# SCH_Project-SappY_2026-01-23.net
KiCad netlist of a schematic drawn in EasyEDA
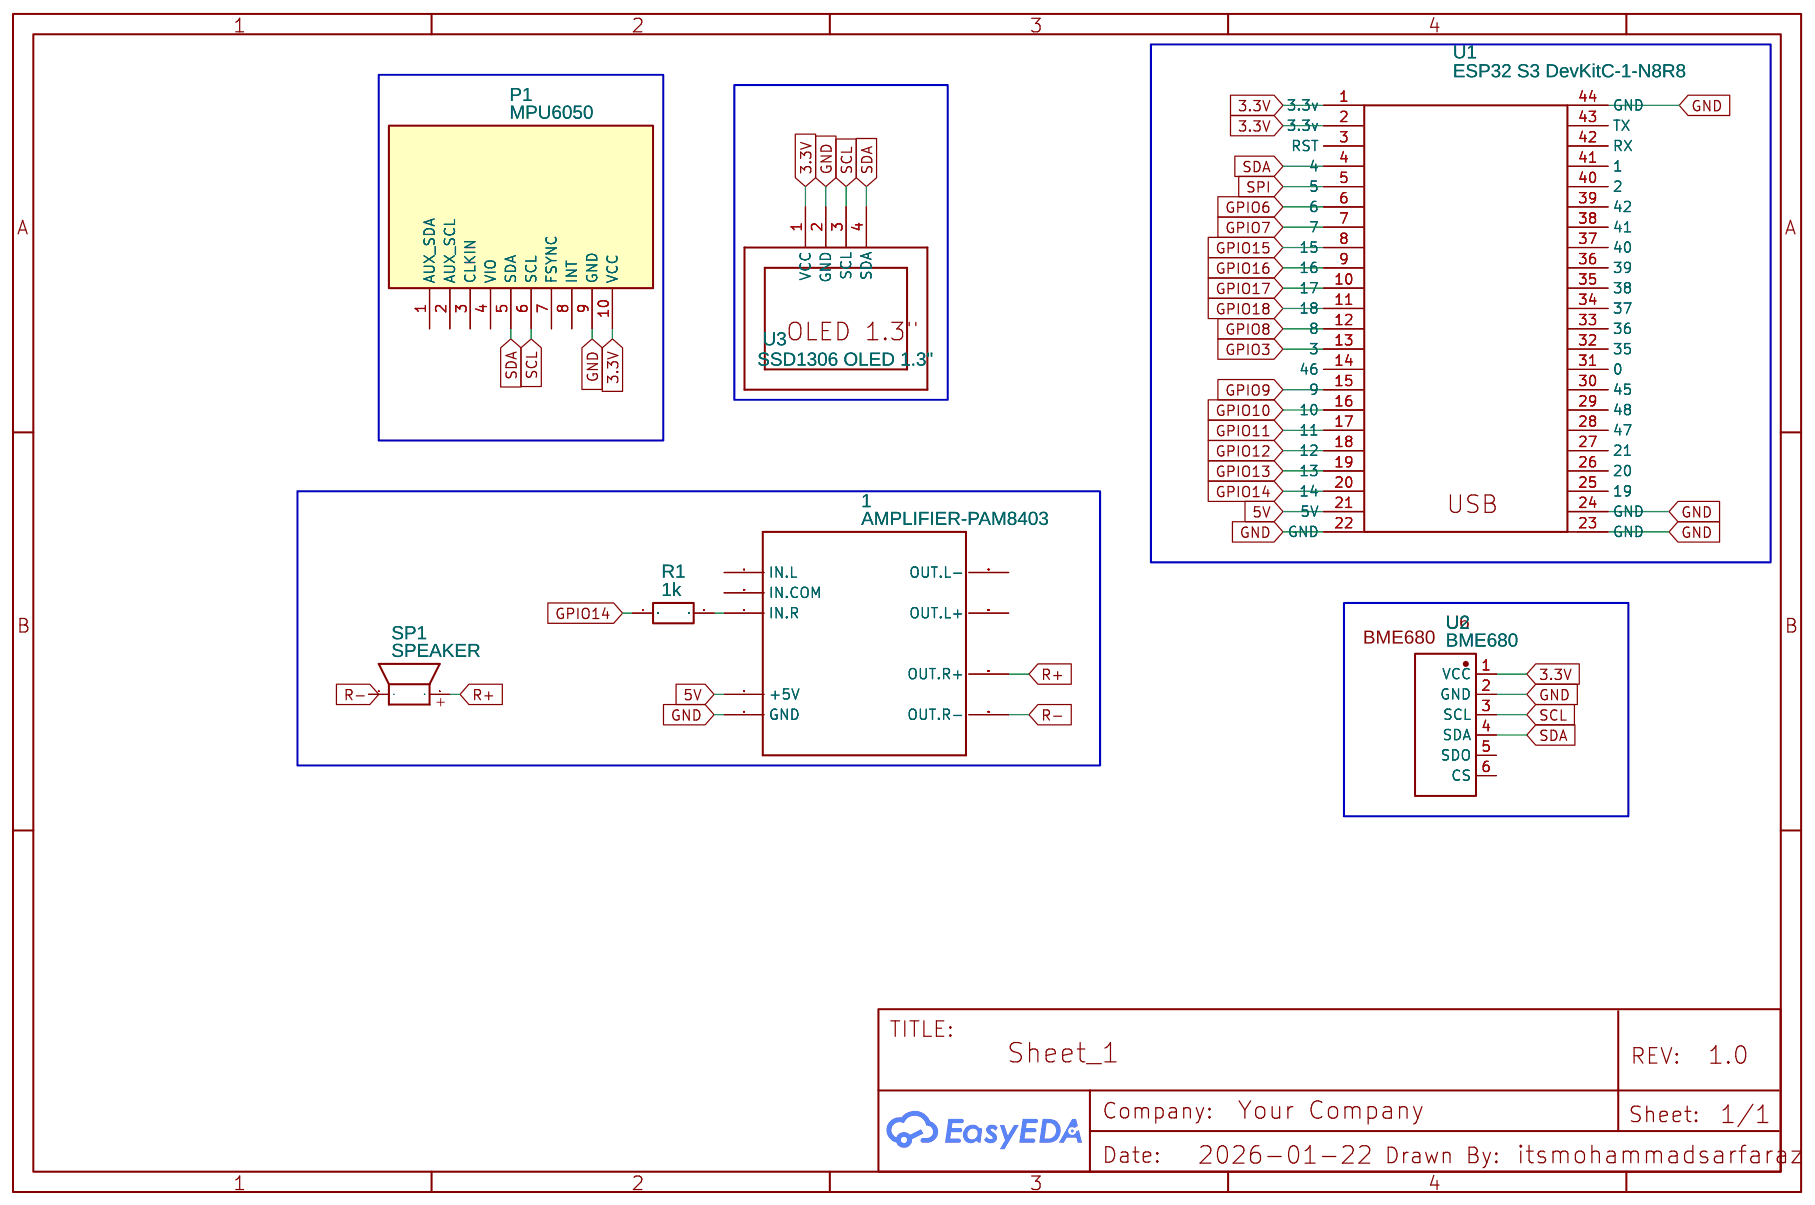
[diagram p0: schematic sheet]

(export (version "E")
  (design (tool "Eeschema 10.0.6"))
  (components
    (comp (ref "1") (value "AMPLIFIER-PAM8403") (libsource (lib "") (part "AMPLIFIER-PAM8403")))
    (comp (ref "P1") (value "MPU6050") (libsource (lib "") (part "MPU6050")))
    (comp (ref "R1") (value "1k") (libsource (lib "") (part "R_0603_EU")))
    (comp (ref "SP1") (value "SPEAKER") (libsource (lib "") (part "SPEAKER")))
    (comp (ref "U1") (value "ESP32 S3 DevKitC-1-N8R8") (libsource (lib "") (part "ESP32 S3 DevKitC-1-N8R8")))
    (comp (ref "U2") (value "BME680") (libsource (lib "") (part "BME680")))
    (comp (ref "U3") (value "SSD1306 OLED 1.3\"") (libsource (lib "") (part "SSD1306 OLED 1.3{dblquote}")))
  )
  (nets
    (net (code "1") (name "3.3V") (class "Default")
      (node (ref "P1") (pin "10") (pinfunction "VCC_10") (pintype "unspecified"))
      (node (ref "U1") (pin "1") (pinfunction "3.3v_1") (pintype "unspecified"))
      (node (ref "U1") (pin "2") (pinfunction "3.3v_2") (pintype "unspecified"))
      (node (ref "U2") (pin "1") (pinfunction "VCC_1") (pintype "unspecified"))
      (node (ref "U3") (pin "1") (pinfunction "VCC_1") (pintype "bidirectional"))
    )
    (net (code "2") (name "5V") (class "Default")
      (node (ref "1") (pin "+5V") (pinfunction "+5V_+5V") (pintype "bidirectional"))
      (node (ref "U1") (pin "21") (pinfunction "5V_21") (pintype "unspecified"))
    )
    (net (code "3") (name "GND") (class "Default")
      (node (ref "1") (pin "GND") (pinfunction "GND_GND") (pintype "bidirectional"))
      (node (ref "P1") (pin "9") (pinfunction "GND_9") (pintype "unspecified"))
      (node (ref "U1") (pin "22") (pinfunction "GND_22") (pintype "unspecified"))
      (node (ref "U1") (pin "24") (pinfunction "GND_24") (pintype "unspecified"))
      (node (ref "U1") (pin "44") (pinfunction "GND_44") (pintype "unspecified"))
      (node (ref "U2") (pin "2") (pinfunction "GND_2") (pintype "unspecified"))
      (node (ref "U3") (pin "2") (pinfunction "GND_2") (pintype "bidirectional"))
    )
    (net (code "4") (name "GPIO3") (class "Default")
      (node (ref "U1") (pin "13") (pinfunction "3_13") (pintype "unspecified"))
    )
    (net (code "5") (name "GPIO6") (class "Default")
      (node (ref "U1") (pin "6") (pinfunction "6_6") (pintype "unspecified"))
    )
    (net (code "6") (name "GPIO7") (class "Default")
      (node (ref "U1") (pin "7") (pinfunction "7_7") (pintype "unspecified"))
    )
    (net (code "7") (name "GPIO8") (class "Default")
      (node (ref "U1") (pin "12") (pinfunction "8_12") (pintype "unspecified"))
    )
    (net (code "8") (name "GPIO9") (class "Default")
      (node (ref "U1") (pin "15") (pinfunction "9_15") (pintype "unspecified"))
    )
    (net (code "9") (name "GPIO10") (class "Default")
      (node (ref "U1") (pin "16") (pinfunction "10_16") (pintype "unspecified"))
    )
    (net (code "10") (name "GPIO11") (class "Default")
      (node (ref "U1") (pin "17") (pinfunction "11_17") (pintype "unspecified"))
    )
    (net (code "11") (name "GPIO12") (class "Default")
      (node (ref "U1") (pin "18") (pinfunction "12_18") (pintype "unspecified"))
    )
    (net (code "12") (name "GPIO13") (class "Default")
      (node (ref "U1") (pin "19") (pinfunction "13_19") (pintype "unspecified"))
    )
    (net (code "13") (name "GPIO14") (class "Default")
      (node (ref "R1") (pin "1") (pinfunction "1_1") (pintype "unspecified"))
      (node (ref "U1") (pin "20") (pinfunction "14_20") (pintype "unspecified"))
    )
    (net (code "14") (name "GPIO15") (class "Default")
      (node (ref "U1") (pin "8") (pinfunction "15_8") (pintype "unspecified"))
    )
    (net (code "15") (name "GPIO16") (class "Default")
      (node (ref "U1") (pin "9") (pinfunction "16_9") (pintype "unspecified"))
    )
    (net (code "16") (name "GPIO17") (class "Default")
      (node (ref "U1") (pin "10") (pinfunction "17_10") (pintype "unspecified"))
    )
    (net (code "17") (name "GPIO18") (class "Default")
      (node (ref "U1") (pin "11") (pinfunction "18_11") (pintype "unspecified"))
    )
    (net (code "18") (name "Net-(1-PadIN.R)") (class "Default")
      (node (ref "1") (pin "IN.R") (pinfunction "IN.R_IN.R") (pintype "bidirectional"))
      (node (ref "R1") (pin "2") (pinfunction "2_2") (pintype "unspecified"))
    )
    (net (code "19") (name "R+") (class "Default")
      (node (ref "1") (pin "OUT.R+") (pinfunction "OUT.R+_OUT.R+") (pintype "bidirectional"))
      (node (ref "SP1") (pin "1") (pinfunction "+_1") (pintype "unspecified"))
    )
    (net (code "20") (name "R-") (class "Default")
      (node (ref "1") (pin "OUT.R-") (pinfunction "OUT.R-_OUT.R-") (pintype "bidirectional"))
      (node (ref "SP1") (pin "2") (pinfunction "-_2") (pintype "unspecified"))
    )
    (net (code "21") (name "SCL") (class "Default")
      (node (ref "P1") (pin "6") (pinfunction "SCL_6") (pintype "unspecified"))
      (node (ref "U2") (pin "3") (pinfunction "SCL_3") (pintype "unspecified"))
      (node (ref "U3") (pin "3") (pinfunction "SCL_3") (pintype "bidirectional"))
    )
    (net (code "22") (name "SDA") (class "Default")
      (node (ref "P1") (pin "5") (pinfunction "SDA_5") (pintype "unspecified"))
      (node (ref "U1") (pin "4") (pinfunction "4_4") (pintype "unspecified"))
      (node (ref "U2") (pin "4") (pinfunction "SDA_4") (pintype "unspecified"))
      (node (ref "U3") (pin "4") (pinfunction "SDA_4") (pintype "bidirectional"))
    )
    (net (code "23") (name "SPI") (class "Default")
      (node (ref "U1") (pin "5") (pinfunction "5_5") (pintype "unspecified"))
    )
    (net (code "24") (name "unconnected-(1-PadIN.COM)") (class "Default")
      (node (ref "1") (pin "IN.COM") (pinfunction "IN.COM_IN.COM") (pintype "bidirectional"))
    )
    (net (code "25") (name "unconnected-(1-PadIN.L)") (class "Default")
      (node (ref "1") (pin "IN.L") (pinfunction "IN.L_IN.L") (pintype "bidirectional"))
    )
    (net (code "26") (name "unconnected-(1-PadOUT.L+)") (class "Default")
      (node (ref "1") (pin "OUT.L+") (pinfunction "OUT.L+_OUT.L+") (pintype "bidirectional"))
    )
    (net (code "27") (name "unconnected-(1-PadOUT.L-)") (class "Default")
      (node (ref "1") (pin "OUT.L-") (pinfunction "OUT.L-_OUT.L-") (pintype "bidirectional"))
    )
    (net (code "28") (name "unconnected-(P1-AUX_SCL-Pad2)") (class "Default")
      (node (ref "P1") (pin "2") (pinfunction "AUX_SCL_2") (pintype "unspecified"))
    )
    (net (code "29") (name "unconnected-(P1-AUX_SDA-Pad1)") (class "Default")
      (node (ref "P1") (pin "1") (pinfunction "AUX_SDA_1") (pintype "unspecified"))
    )
    (net (code "30") (name "unconnected-(P1-CLKIN-Pad3)") (class "Default")
      (node (ref "P1") (pin "3") (pinfunction "CLKIN_3") (pintype "unspecified"))
    )
    (net (code "31") (name "unconnected-(P1-FSYNC-Pad7)") (class "Default")
      (node (ref "P1") (pin "7") (pinfunction "FSYNC_7") (pintype "unspecified"))
    )
    (net (code "32") (name "unconnected-(P1-INT-Pad8)") (class "Default")
      (node (ref "P1") (pin "8") (pinfunction "INT_8") (pintype "unspecified"))
    )
    (net (code "33") (name "unconnected-(P1-VIO-Pad4)") (class "Default")
      (node (ref "P1") (pin "4") (pinfunction "VIO_4") (pintype "unspecified"))
    )
    (net (code "34") (name "unconnected-(U1-0-Pad31)") (class "Default")
      (node (ref "U1") (pin "31") (pinfunction "0_31") (pintype "unspecified"))
    )
    (net (code "35") (name "unconnected-(U1-1-Pad41)") (class "Default")
      (node (ref "U1") (pin "41") (pinfunction "1_41") (pintype "unspecified"))
    )
    (net (code "36") (name "unconnected-(U1-2-Pad40)") (class "Default")
      (node (ref "U1") (pin "40") (pinfunction "2_40") (pintype "unspecified"))
    )
    (net (code "37") (name "unconnected-(U1-19-Pad25)") (class "Default")
      (node (ref "U1") (pin "25") (pinfunction "19_25") (pintype "unspecified"))
    )
    (net (code "38") (name "unconnected-(U1-20-Pad26)") (class "Default")
      (node (ref "U1") (pin "26") (pinfunction "20_26") (pintype "unspecified"))
    )
    (net (code "39") (name "unconnected-(U1-21-Pad27)") (class "Default")
      (node (ref "U1") (pin "27") (pinfunction "21_27") (pintype "unspecified"))
    )
    (net (code "40") (name "unconnected-(U1-35-Pad32)") (class "Default")
      (node (ref "U1") (pin "32") (pinfunction "35_32") (pintype "unspecified"))
    )
    (net (code "41") (name "unconnected-(U1-36-Pad33)") (class "Default")
      (node (ref "U1") (pin "33") (pinfunction "36_33") (pintype "unspecified"))
    )
    (net (code "42") (name "unconnected-(U1-37-Pad34)") (class "Default")
      (node (ref "U1") (pin "34") (pinfunction "37_34") (pintype "unspecified"))
    )
    (net (code "43") (name "unconnected-(U1-38-Pad35)") (class "Default")
      (node (ref "U1") (pin "35") (pinfunction "38_35") (pintype "unspecified"))
    )
    (net (code "44") (name "unconnected-(U1-39-Pad36)") (class "Default")
      (node (ref "U1") (pin "36") (pinfunction "39_36") (pintype "unspecified"))
    )
    (net (code "45") (name "unconnected-(U1-40-Pad37)") (class "Default")
      (node (ref "U1") (pin "37") (pinfunction "40_37") (pintype "unspecified"))
    )
    (net (code "46") (name "unconnected-(U1-41-Pad38)") (class "Default")
      (node (ref "U1") (pin "38") (pinfunction "41_38") (pintype "unspecified"))
    )
    (net (code "47") (name "unconnected-(U1-42-Pad39)") (class "Default")
      (node (ref "U1") (pin "39") (pinfunction "42_39") (pintype "unspecified"))
    )
    (net (code "48") (name "unconnected-(U1-45-Pad30)") (class "Default")
      (node (ref "U1") (pin "30") (pinfunction "45_30") (pintype "unspecified"))
    )
    (net (code "49") (name "unconnected-(U1-46-Pad14)") (class "Default")
      (node (ref "U1") (pin "14") (pinfunction "46_14") (pintype "unspecified"))
    )
    (net (code "50") (name "unconnected-(U1-47-Pad28)") (class "Default")
      (node (ref "U1") (pin "28") (pinfunction "47_28") (pintype "unspecified"))
    )
    (net (code "51") (name "unconnected-(U1-48-Pad29)") (class "Default")
      (node (ref "U1") (pin "29") (pinfunction "48_29") (pintype "unspecified"))
    )
    (net (code "52") (name "unconnected-(U1-GND-Pad23)") (class "Default")
      (node (ref "U1") (pin "23") (pinfunction "GND_23") (pintype "unspecified"))
    )
    (net (code "53") (name "unconnected-(U1-RST-Pad3)") (class "Default")
      (node (ref "U1") (pin "3") (pinfunction "RST_3") (pintype "unspecified"))
    )
    (net (code "54") (name "unconnected-(U1-RX-Pad42)") (class "Default")
      (node (ref "U1") (pin "42") (pinfunction "RX_42") (pintype "unspecified"))
    )
    (net (code "55") (name "unconnected-(U1-TX-Pad43)") (class "Default")
      (node (ref "U1") (pin "43") (pinfunction "TX_43") (pintype "unspecified"))
    )
    (net (code "56") (name "unconnected-(U2-CS-Pad6)") (class "Default")
      (node (ref "U2") (pin "6") (pinfunction "CS_6") (pintype "unspecified"))
    )
    (net (code "57") (name "unconnected-(U2-SDO-Pad5)") (class "Default")
      (node (ref "U2") (pin "5") (pinfunction "SDO_5") (pintype "unspecified"))
    )
  )
)
